# V_16.net
KiCad netlist of a schematic drawn in Altium Designer
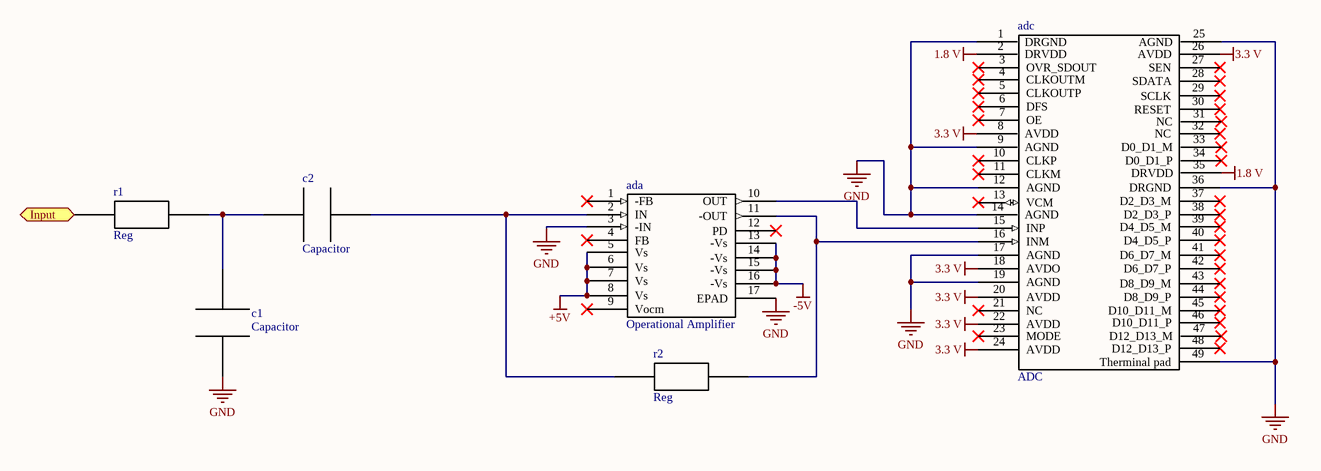
[diagram p0: V_16.SchDoc]

(export (version "E")
  (design (tool "Eeschema 10.0.6"))
  (components
    (comp (ref "ada")
      (value "Operational Amplifier")
      (footprint "V_16:ADA4932-1")
      (libsource (lib "V_16") (part "Operational Amplifier"))
    )
    (comp (ref "adc") (value "ADC") (footprint "ADS61b49") (libsource (lib "V_16") (part "ADC")))
    (comp (ref "c1") (value "Capacitor") (footprint "Ñ") (libsource (lib "V_16") (part "Capacitor")))
    (comp (ref "c2") (value "Capacitor") (footprint "V_16:Ñ") (libsource (lib "V_16") (part "Capacitor")))
    (comp (ref "r1") (value "Reg") (footprint "V_16:R_0.0085") (libsource (lib "V_16") (part "Reg")))
    (comp (ref "r2") (value "Reg") (footprint "V_16:R_0.0085") (libsource (lib "V_16") (part "Reg")))
  )
  (nets
    (net (code "1") (name "+5V") (class "Default")
      (node (ref "ada") (pin "5") (pinfunction "Vs_5") (pintype "passive"))
      (node (ref "ada") (pin "6") (pinfunction "Vs_6") (pintype "passive"))
      (node (ref "ada") (pin "7") (pinfunction "Vs_7") (pintype "passive"))
      (node (ref "ada") (pin "8") (pinfunction "Vs_8") (pintype "passive"))
    )
    (net (code "2") (name "-5V") (class "Default")
      (node (ref "ada") (pin "13") (pinfunction "-Vs_13") (pintype "passive"))
      (node (ref "ada") (pin "14") (pinfunction "-Vs_14") (pintype "passive"))
      (node (ref "ada") (pin "15") (pinfunction "-Vs_15") (pintype "passive"))
      (node (ref "ada") (pin "16") (pinfunction "-Vs_16") (pintype "passive"))
    )
    (net (code "3") (name "/Input") (class "Default")
      (node (ref "r1") (pin "1") (pinfunction "1_1") (pintype "passive"))
    )
    (net (code "4") (name "1.8 V") (class "Default")
      (node (ref "adc") (pin "2") (pinfunction "DRVDD_2") (pintype "passive"))
      (node (ref "adc") (pin "35") (pinfunction "DRVDD_35") (pintype "passive"))
    )
    (net (code "5") (name "3.3 V") (class "Default")
      (node (ref "adc") (pin "18") (pinfunction "AVDO_18") (pintype "passive"))
      (node (ref "adc") (pin "20") (pinfunction "AVDD_20") (pintype "passive"))
      (node (ref "adc") (pin "22") (pinfunction "AVDD_22") (pintype "passive"))
      (node (ref "adc") (pin "24") (pinfunction "AVDD_24") (pintype "passive"))
      (node (ref "adc") (pin "26") (pinfunction "AVDD_26") (pintype "passive"))
      (node (ref "adc") (pin "8") (pinfunction "AVDD_8") (pintype "passive"))
    )
    (net (code "6") (name "GND") (class "Default")
      (node (ref "ada") (pin "17") (pinfunction "EPAD_17") (pintype "power_in"))
      (node (ref "ada") (pin "3") (pinfunction "-IN_3") (pintype "input"))
      (node (ref "adc") (pin "1") (pinfunction "DRGND_1") (pintype "passive"))
      (node (ref "adc") (pin "12") (pinfunction "AGND_12") (pintype "passive"))
      (node (ref "adc") (pin "14") (pinfunction "AGND_14") (pintype "passive"))
      (node (ref "adc") (pin "17") (pinfunction "AGND_17") (pintype "passive"))
      (node (ref "adc") (pin "19") (pinfunction "AGND_19") (pintype "passive"))
      (node (ref "adc") (pin "25") (pinfunction "AGND_25") (pintype "passive"))
      (node (ref "adc") (pin "36") (pinfunction "DRGND_36") (pintype "passive"))
      (node (ref "adc") (pin "49") (pinfunction "Therminal_pad_49") (pintype "passive"))
      (node (ref "adc") (pin "9") (pinfunction "AGND_9") (pintype "passive"))
      (node (ref "c1") (pin "1") (pinfunction "1_1") (pintype "passive"))
    )
    (net (code "7") (name "Net-(ada--OUT)") (class "Default")
      (node (ref "ada") (pin "11") (pinfunction "-OUT_11") (pintype "output"))
      (node (ref "adc") (pin "16") (pinfunction "INM_16") (pintype "input"))
      (node (ref "r2") (pin "2") (pinfunction "2_2") (pintype "passive"))
    )
    (net (code "8") (name "Net-(ada-IN)") (class "Default")
      (node (ref "ada") (pin "2") (pinfunction "IN_2") (pintype "input"))
      (node (ref "c2") (pin "2") (pinfunction "2_2") (pintype "passive"))
      (node (ref "r2") (pin "1") (pinfunction "1_1") (pintype "passive"))
    )
    (net (code "9") (name "Net-(ada-OUT)") (class "Default")
      (node (ref "ada") (pin "10") (pinfunction "OUT_10") (pintype "output"))
      (node (ref "adc") (pin "15") (pinfunction "INP_15") (pintype "input"))
    )
    (net (code "10") (name "Net-(c1-Pad2)") (class "Default")
      (node (ref "c1") (pin "2") (pinfunction "2_2") (pintype "passive"))
      (node (ref "c2") (pin "1") (pinfunction "1_1") (pintype "passive"))
      (node (ref "r1") (pin "2") (pinfunction "2_2") (pintype "passive"))
    )
    (net (code "11") (name "unconnected-(ada--FB-Pad1)") (class "Default")
      (node (ref "ada") (pin "1") (pinfunction "-FB_1") (pintype "input+no_connect"))
    )
    (net (code "12") (name "unconnected-(ada-FB-Pad4)") (class "Default")
      (node (ref "ada") (pin "4") (pinfunction "FB_4") (pintype "passive+no_connect"))
    )
    (net (code "13") (name "unconnected-(ada-PD-Pad12)") (class "Default")
      (node (ref "ada") (pin "12") (pinfunction "PD_12") (pintype "passive+no_connect"))
    )
    (net (code "14") (name "unconnected-(ada-Vocm-Pad9)") (class "Default")
      (node (ref "ada") (pin "9") (pinfunction "Vocm_9") (pintype "passive+no_connect"))
    )
    (net (code "15") (name "unconnected-(adc-CLKM-Pad11)") (class "Default")
      (node (ref "adc") (pin "11") (pinfunction "CLKM_11") (pintype "passive+no_connect"))
    )
    (net (code "16") (name "unconnected-(adc-CLKOUTM-Pad4)") (class "Default")
      (node (ref "adc") (pin "4") (pinfunction "CLKOUTM_4") (pintype "passive+no_connect"))
    )
    (net (code "17") (name "unconnected-(adc-CLKOUTP-Pad5)") (class "Default")
      (node (ref "adc") (pin "5") (pinfunction "CLKOUTP_5") (pintype "passive+no_connect"))
    )
    (net (code "18") (name "unconnected-(adc-CLKP-Pad10)") (class "Default")
      (node (ref "adc") (pin "10") (pinfunction "CLKP_10") (pintype "passive+no_connect"))
    )
    (net (code "19") (name "unconnected-(adc-D0_D1_M-Pad33)") (class "Default")
      (node (ref "adc") (pin "33") (pinfunction "D0_D1_M_33") (pintype "passive+no_connect"))
    )
    (net (code "20") (name "unconnected-(adc-D0_D1_P-Pad34)") (class "Default")
      (node (ref "adc") (pin "34") (pinfunction "D0_D1_P_34") (pintype "passive+no_connect"))
    )
    (net (code "21") (name "unconnected-(adc-D2_D3_M-Pad37)") (class "Default")
      (node (ref "adc") (pin "37") (pinfunction "D2_D3_M_37") (pintype "passive+no_connect"))
    )
    (net (code "22") (name "unconnected-(adc-D2_D3_P-Pad38)") (class "Default")
      (node (ref "adc") (pin "38") (pinfunction "D2_D3_P_38") (pintype "passive+no_connect"))
    )
    (net (code "23") (name "unconnected-(adc-D4_D5_M-Pad39)") (class "Default")
      (node (ref "adc") (pin "39") (pinfunction "D4_D5_M_39") (pintype "passive+no_connect"))
    )
    (net (code "24") (name "unconnected-(adc-D4_D5_P-Pad40)") (class "Default")
      (node (ref "adc") (pin "40") (pinfunction "D4_D5_P_40") (pintype "passive+no_connect"))
    )
    (net (code "25") (name "unconnected-(adc-D6_D7_M-Pad41)") (class "Default")
      (node (ref "adc") (pin "41") (pinfunction "D6_D7_M_41") (pintype "passive+no_connect"))
    )
    (net (code "26") (name "unconnected-(adc-D6_D7_P-Pad42)") (class "Default")
      (node (ref "adc") (pin "42") (pinfunction "D6_D7_P_42") (pintype "passive+no_connect"))
    )
    (net (code "27") (name "unconnected-(adc-D8_D9_M-Pad43)") (class "Default")
      (node (ref "adc") (pin "43") (pinfunction "D8_D9_M_43") (pintype "passive+no_connect"))
    )
    (net (code "28") (name "unconnected-(adc-D8_D9_P-Pad44)") (class "Default")
      (node (ref "adc") (pin "44") (pinfunction "D8_D9_P_44") (pintype "passive+no_connect"))
    )
    (net (code "29") (name "unconnected-(adc-D10_D11_M-Pad45)") (class "Default")
      (node (ref "adc") (pin "45") (pinfunction "D10_D11_M_45") (pintype "passive+no_connect"))
    )
    (net (code "30") (name "unconnected-(adc-D10_D11_P-Pad46)") (class "Default")
      (node (ref "adc") (pin "46") (pinfunction "D10_D11_P_46") (pintype "passive+no_connect"))
    )
    (net (code "31") (name "unconnected-(adc-D12_D13_M-Pad47)") (class "Default")
      (node (ref "adc") (pin "47") (pinfunction "D12_D13_M_47") (pintype "passive+no_connect"))
    )
    (net (code "32") (name "unconnected-(adc-D12_D13_P-Pad48)") (class "Default")
      (node (ref "adc") (pin "48") (pinfunction "D12_D13_P_48") (pintype "passive+no_connect"))
    )
    (net (code "33") (name "unconnected-(adc-DFS-Pad6)") (class "Default")
      (node (ref "adc") (pin "6") (pinfunction "DFS_6") (pintype "passive+no_connect"))
    )
    (net (code "34") (name "unconnected-(adc-MODE-Pad23)") (class "Default")
      (node (ref "adc") (pin "23") (pinfunction "MODE_23") (pintype "passive+no_connect"))
    )
    (net (code "35") (name "unconnected-(adc-NC-Pad21)") (class "Default")
      (node (ref "adc") (pin "21") (pinfunction "NC_21") (pintype "passive+no_connect"))
    )
    (net (code "36") (name "unconnected-(adc-NC-Pad31)") (class "Default")
      (node (ref "adc") (pin "31") (pinfunction "NC_31") (pintype "passive+no_connect"))
    )
    (net (code "37") (name "unconnected-(adc-NC-Pad32)") (class "Default")
      (node (ref "adc") (pin "32") (pinfunction "NC_32") (pintype "passive+no_connect"))
    )
    (net (code "38") (name "unconnected-(adc-OE-Pad7)") (class "Default")
      (node (ref "adc") (pin "7") (pinfunction "OE_7") (pintype "passive+no_connect"))
    )
    (net (code "39") (name "unconnected-(adc-OVR_SDOUT-Pad3)") (class "Default")
      (node (ref "adc") (pin "3") (pinfunction "OVR_SDOUT_3") (pintype "passive+no_connect"))
    )
    (net (code "40") (name "unconnected-(adc-RESET-Pad30)") (class "Default")
      (node (ref "adc") (pin "30") (pinfunction "RESET_30") (pintype "passive+no_connect"))
    )
    (net (code "41") (name "unconnected-(adc-SCLK-Pad29)") (class "Default")
      (node (ref "adc") (pin "29") (pinfunction "SCLK_29") (pintype "passive+no_connect"))
    )
    (net (code "42") (name "unconnected-(adc-SDATA-Pad28)") (class "Default")
      (node (ref "adc") (pin "28") (pinfunction "SDATA_28") (pintype "passive+no_connect"))
    )
    (net (code "43") (name "unconnected-(adc-SEN-Pad27)") (class "Default")
      (node (ref "adc") (pin "27") (pinfunction "SEN_27") (pintype "passive+no_connect"))
    )
    (net (code "44") (name "unconnected-(adc-VCM-Pad13)") (class "Default")
      (node (ref "adc") (pin "13") (pinfunction "VCM_13") (pintype "bidirectional+no_connect"))
    )
  )
)
